# minna_schematic_io.net
KiCad netlist of a schematic drawn in Altium Designer
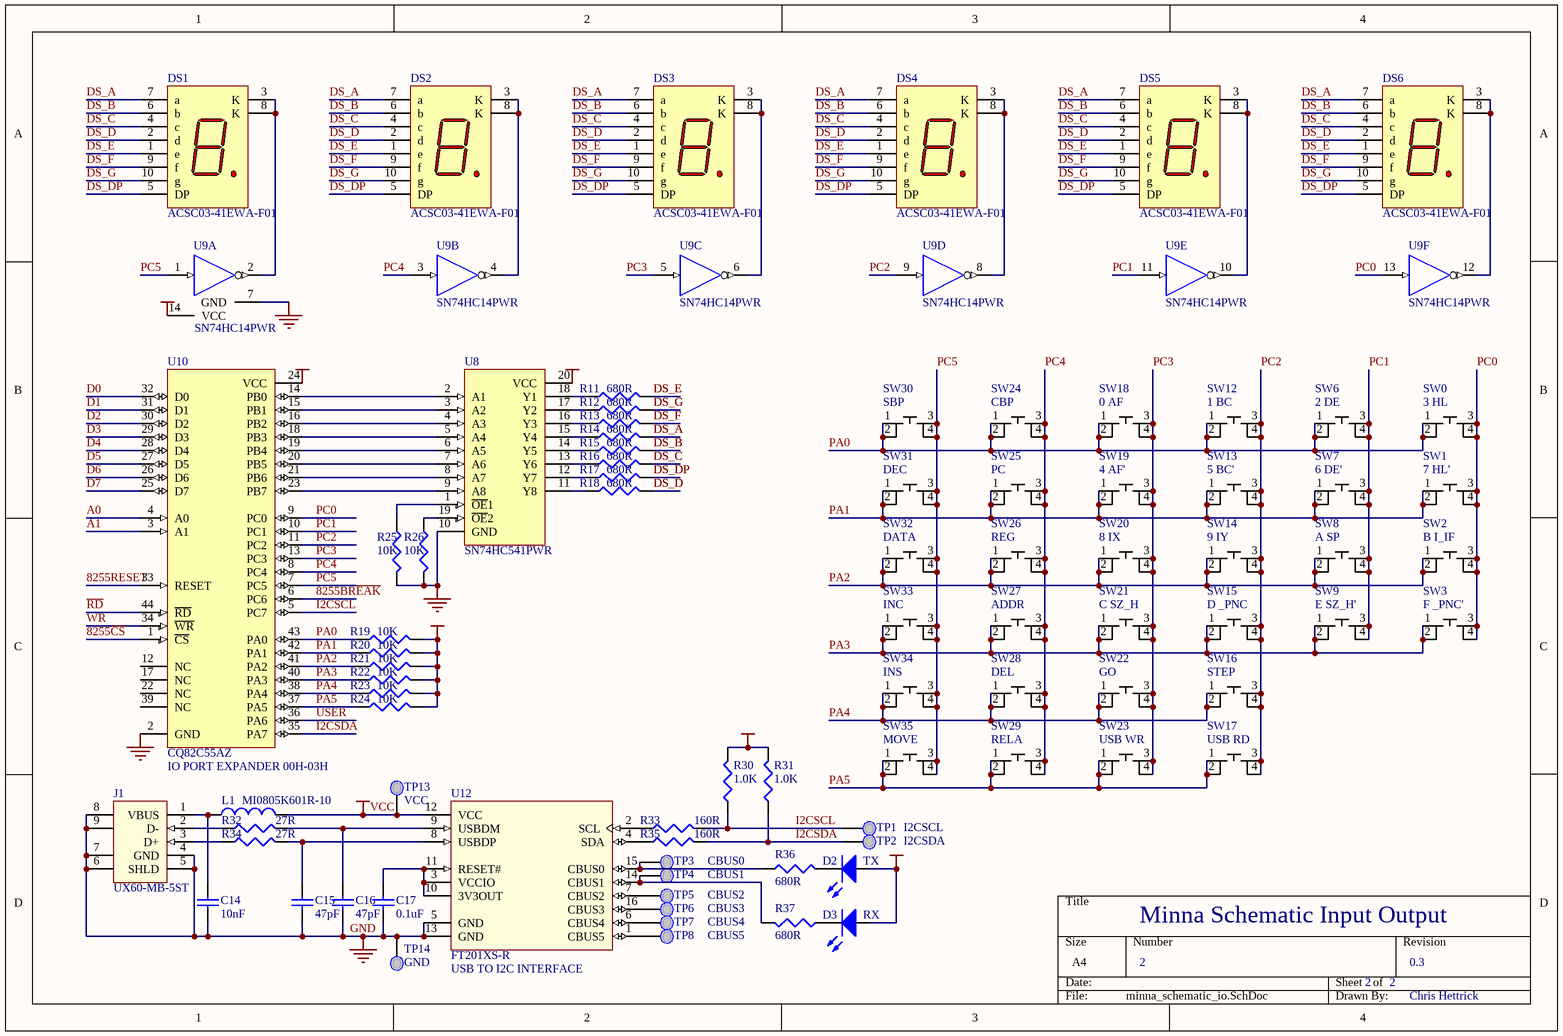
[diagram p0: minna_schematic_io.SchDoc]

(export (version "E")
  (design (tool "Eeschema 10.0.6"))
  (components
    (comp (ref "C14")
      (value "10nF")
      (footprint "smari_lib_pcb:0603")
      (description "CAP CER 10000PF 50V 10% X7R 0603")
      (libsource (lib "smari_lib_schematic") (part "C0603"))
    )
    (comp (ref "C15")
      (value "47pF")
      (footprint "smari_lib_pcb:0603")
      (description "CAP CER 47PF 50V 5% NP0 0603")
      (libsource (lib "smari_lib_schematic") (part "C0603"))
    )
    (comp (ref "C16")
      (value "47pF")
      (footprint "smari_lib_pcb:0603")
      (description "CAP CER 47PF 50V 5% NP0 0603")
      (libsource (lib "smari_lib_schematic") (part "C0603"))
    )
    (comp (ref "C17")
      (value "0.1uF")
      (footprint "smari_lib_pcb:0603")
      (description "CAP .10UF 16V CERAMIC X7R 0603")
      (libsource (lib "smari_lib_schematic") (part "C0603"))
    )
    (comp (ref "D2")
      (value "TX")
      (footprint "smari_lib_pcb:APG1608")
      (description "LED SUPER RED CLEAR 0603 SMD")
      (libsource (lib "smari_lib_schematic") (part "LTST-C190KRKT"))
    )
    (comp (ref "D3")
      (value "RX")
      (footprint "smari_lib_pcb:APG1608")
      (description "LED SUPER RED CLEAR 0603 SMD")
      (libsource (lib "smari_lib_schematic") (part "LTST-C190KRKT"))
    )
    (comp (ref "DS1")
      (value "ACSC03-41EWA-F01")
      (footprint "Minna Project:ACSC03-41EWA-F01")
      (description "DISPLAY 0.3\" 627NM SGL RED SMD")
      (libsource (lib "smari_lib_schematic") (part "ACSC03-41EWA-F01"))
    )
    (comp (ref "DS2")
      (value "ACSC03-41EWA-F01")
      (footprint "Minna Project:ACSC03-41EWA-F01")
      (description "DISPLAY 0.3\" 627NM SGL RED SMD")
      (libsource (lib "smari_lib_schematic") (part "ACSC03-41EWA-F01"))
    )
    (comp (ref "DS3")
      (value "ACSC03-41EWA-F01")
      (footprint "Minna Project:ACSC03-41EWA-F01")
      (description "DISPLAY 0.3\" 627NM SGL RED SMD")
      (libsource (lib "smari_lib_schematic") (part "ACSC03-41EWA-F01"))
    )
    (comp (ref "DS4")
      (value "ACSC03-41EWA-F01")
      (footprint "Minna Project:ACSC03-41EWA-F01")
      (description "DISPLAY 0.3\" 627NM SGL RED SMD")
      (libsource (lib "smari_lib_schematic") (part "ACSC03-41EWA-F01"))
    )
    (comp (ref "DS5")
      (value "ACSC03-41EWA-F01")
      (footprint "Minna Project:ACSC03-41EWA-F01")
      (description "DISPLAY 0.3\" 627NM SGL RED SMD")
      (libsource (lib "smari_lib_schematic") (part "ACSC03-41EWA-F01"))
    )
    (comp (ref "DS6")
      (value "ACSC03-41EWA-F01")
      (footprint "Minna Project:ACSC03-41EWA-F01")
      (description "DISPLAY 0.3\" 627NM SGL RED SMD")
      (libsource (lib "smari_lib_schematic") (part "ACSC03-41EWA-F01"))
    )
    (comp (ref "J1")
      (value "UX60-MB-5ST")
      (footprint "smari_lib_pcb:UX60-MB-5ST")
      (description "CONN RECEPT MINI USB2.0 5POS")
      (libsource (lib "smari_lib_schematic") (part "UX60-MB-5ST"))
    )
    (comp (ref "L1")
      (value "MI0805K601R-10")
      (footprint "smari_lib_pcb:0805")
      (description "FERRITE CHIP POWER 600 OHM SMD")
      (libsource (lib "smari_lib_schematic") (part "MI0805K601R-10"))
    )
    (comp (ref "R11")
      (value "680R")
      (footprint "Minna Project:0603")
      (description "RES 680 OHM 1/10W 1% 0603 SMD")
      (libsource (lib "smari_lib_schematic") (part "MCR03EZPFX"))
    )
    (comp (ref "R12")
      (value "680R")
      (footprint "Minna Project:0603")
      (description "RES 680 OHM 1/10W 1% 0603 SMD")
      (libsource (lib "smari_lib_schematic") (part "MCR03EZPFX"))
    )
    (comp (ref "R13")
      (value "680R")
      (footprint "Minna Project:0603")
      (description "RES 680 OHM 1/10W 1% 0603 SMD")
      (libsource (lib "smari_lib_schematic") (part "MCR03EZPFX"))
    )
    (comp (ref "R14")
      (value "680R")
      (footprint "Minna Project:0603")
      (description "RES 680 OHM 1/10W 1% 0603 SMD")
      (libsource (lib "smari_lib_schematic") (part "MCR03EZPFX"))
    )
    (comp (ref "R15")
      (value "680R")
      (footprint "Minna Project:0603")
      (description "RES 680 OHM 1/10W 1% 0603 SMD")
      (libsource (lib "smari_lib_schematic") (part "MCR03EZPFX"))
    )
    (comp (ref "R16")
      (value "680R")
      (footprint "Minna Project:0603")
      (description "RES 680 OHM 1/10W 1% 0603 SMD")
      (libsource (lib "smari_lib_schematic") (part "MCR03EZPFX"))
    )
    (comp (ref "R17")
      (value "680R")
      (footprint "Minna Project:0603")
      (description "RES 680 OHM 1/10W 1% 0603 SMD")
      (libsource (lib "smari_lib_schematic") (part "MCR03EZPFX"))
    )
    (comp (ref "R18")
      (value "680R")
      (footprint "Minna Project:0603")
      (description "RES 680 OHM 1/10W 1% 0603 SMD")
      (libsource (lib "smari_lib_schematic") (part "MCR03EZPFX"))
    )
    (comp (ref "R19")
      (value "10K")
      (footprint "Minna Project:0603")
      (description "RES 10.0K OHM 1/10W 1% 0603 SMD")
      (libsource (lib "smari_lib_schematic") (part "MCR03EZPFX"))
    )
    (comp (ref "R20")
      (value "10K")
      (footprint "Minna Project:0603")
      (description "RES 10.0K OHM 1/10W 1% 0603 SMD")
      (libsource (lib "smari_lib_schematic") (part "MCR03EZPFX"))
    )
    (comp (ref "R21")
      (value "10K")
      (footprint "Minna Project:0603")
      (description "RES 10.0K OHM 1/10W 1% 0603 SMD")
      (libsource (lib "smari_lib_schematic") (part "MCR03EZPFX"))
    )
    (comp (ref "R22")
      (value "10K")
      (footprint "Minna Project:0603")
      (description "RES 10.0K OHM 1/10W 1% 0603 SMD")
      (libsource (lib "smari_lib_schematic") (part "MCR03EZPFX"))
    )
    (comp (ref "R23")
      (value "10K")
      (footprint "Minna Project:0603")
      (description "RES 10.0K OHM 1/10W 1% 0603 SMD")
      (libsource (lib "smari_lib_schematic") (part "MCR03EZPFX"))
    )
    (comp (ref "R24")
      (value "10K")
      (footprint "Minna Project:0603")
      (description "RES 10.0K OHM 1/10W 1% 0603 SMD")
      (libsource (lib "smari_lib_schematic") (part "MCR03EZPFX"))
    )
    (comp (ref "R25")
      (value "10K")
      (footprint "Minna Project:0603")
      (description "RES 10.0K OHM 1/10W 1% 0603 SMD")
      (libsource (lib "smari_lib_schematic") (part "MCR03EZPFX"))
    )
    (comp (ref "R26")
      (value "10K")
      (footprint "Minna Project:0603")
      (description "RES 10.0K OHM 1/10W 1% 0603 SMD")
      (libsource (lib "smari_lib_schematic") (part "MCR03EZPFX"))
    )
    (comp (ref "R30")
      (value "1.0K")
      (footprint "smari_lib_pcb:0603")
      (description "RES 1.00K OHM 1/10W 1% 0603 SMD")
      (libsource (lib "smari_lib_schematic") (part "ERJ-3EKF1002V"))
    )
    (comp (ref "R31")
      (value "1.0K")
      (footprint "smari_lib_pcb:0603")
      (description "RES 1.00K OHM 1/10W 1% 0603 SMD")
      (libsource (lib "smari_lib_schematic") (part "ERJ-3EKF1002V"))
    )
    (comp (ref "R32")
      (value "27R")
      (footprint "smari_lib_pcb:0603")
      (description "RES 27.0 OHM 1/10W 1% 0603 SMD")
      (libsource (lib "smari_lib_schematic") (part "ERJ-3EKF1002V"))
    )
    (comp (ref "R33")
      (value "160R")
      (footprint "smari_lib_pcb:0603")
      (description "RES 160 OHM 1/10W 1% 0603 SMD")
      (libsource (lib "smari_lib_schematic") (part "ERJ-3EKF1002V"))
    )
    (comp (ref "R34")
      (value "27R")
      (footprint "smari_lib_pcb:0603")
      (description "RES 27.0 OHM 1/10W 1% 0603 SMD")
      (libsource (lib "smari_lib_schematic") (part "ERJ-3EKF1002V"))
    )
    (comp (ref "R35")
      (value "160R")
      (footprint "smari_lib_pcb:0603")
      (description "RES 160 OHM 1/10W 1% 0603 SMD")
      (libsource (lib "smari_lib_schematic") (part "ERJ-3EKF1002V"))
    )
    (comp (ref "R36")
      (value "680R")
      (footprint "smari_lib_pcb:0603")
      (description "RES 680 OHM 1/10W 1% 0603 SMD")
      (libsource (lib "smari_lib_schematic") (part "MCR03EZPFX"))
    )
    (comp (ref "R37")
      (value "680R")
      (footprint "smari_lib_pcb:0603")
      (description "RES 680 OHM 1/10W 1% 0603 SMD")
      (libsource (lib "smari_lib_schematic") (part "MCR03EZPFX"))
    )
    (comp (ref "SW0")
      (value "3 HL")
      (footprint "Minna Project:PTS645SM43SMTR LFS")
      (description "SWITCH TACT 6MM 160GF H=4.3MM")
      (libsource (lib "smari_lib_schematic") (part "PTS645SM43SMTR LFS"))
    )
    (comp (ref "SW1")
      (value "7 HL'")
      (footprint "Minna Project:PTS645SM43SMTR LFS")
      (description "SWITCH TACT 6MM 160GF H=4.3MM")
      (libsource (lib "smari_lib_schematic") (part "PTS645SM43SMTR LFS"))
    )
    (comp (ref "SW2")
      (value "B I_IF")
      (footprint "Minna Project:PTS645SM43SMTR LFS")
      (description "SWITCH TACT 6MM 160GF H=4.3MM")
      (libsource (lib "smari_lib_schematic") (part "PTS645SM43SMTR LFS"))
    )
    (comp (ref "SW3")
      (value "F _PNC'")
      (footprint "Minna Project:PTS645SM43SMTR LFS")
      (description "SWITCH TACT 6MM 160GF H=4.3MM")
      (libsource (lib "smari_lib_schematic") (part "PTS645SM43SMTR LFS"))
    )
    (comp (ref "SW6")
      (value "2 DE")
      (footprint "Minna Project:PTS645SM43SMTR LFS")
      (description "SWITCH TACT 6MM 160GF H=4.3MM")
      (libsource (lib "smari_lib_schematic") (part "PTS645SM43SMTR LFS"))
    )
    (comp (ref "SW7")
      (value "6 DE'")
      (footprint "Minna Project:PTS645SM43SMTR LFS")
      (description "SWITCH TACT 6MM 160GF H=4.3MM")
      (libsource (lib "smari_lib_schematic") (part "PTS645SM43SMTR LFS"))
    )
    (comp (ref "SW8")
      (value "A SP")
      (footprint "Minna Project:PTS645SM43SMTR LFS")
      (description "SWITCH TACT 6MM 160GF H=4.3MM")
      (libsource (lib "smari_lib_schematic") (part "PTS645SM43SMTR LFS"))
    )
    (comp (ref "SW9")
      (value "E SZ_H'")
      (footprint "Minna Project:PTS645SM43SMTR LFS")
      (description "SWITCH TACT 6MM 160GF H=4.3MM")
      (libsource (lib "smari_lib_schematic") (part "PTS645SM43SMTR LFS"))
    )
    (comp (ref "SW12")
      (value "1 BC")
      (footprint "Minna Project:PTS645SM43SMTR LFS")
      (description "SWITCH TACT 6MM 160GF H=4.3MM")
      (libsource (lib "smari_lib_schematic") (part "PTS645SM43SMTR LFS"))
    )
    (comp (ref "SW13")
      (value "5 BC'")
      (footprint "Minna Project:PTS645SM43SMTR LFS")
      (description "SWITCH TACT 6MM 160GF H=4.3MM")
      (libsource (lib "smari_lib_schematic") (part "PTS645SM43SMTR LFS"))
    )
    (comp (ref "SW14")
      (value "9 IY")
      (footprint "Minna Project:PTS645SM43SMTR LFS")
      (description "SWITCH TACT 6MM 160GF H=4.3MM")
      (libsource (lib "smari_lib_schematic") (part "PTS645SM43SMTR LFS"))
    )
    (comp (ref "SW15")
      (value "D _PNC")
      (footprint "Minna Project:PTS645SM43SMTR LFS")
      (description "SWITCH TACT 6MM 160GF H=4.3MM")
      (libsource (lib "smari_lib_schematic") (part "PTS645SM43SMTR LFS"))
    )
    (comp (ref "SW16")
      (value "STEP")
      (footprint "Minna Project:PTS645SM43SMTR LFS")
      (description "SWITCH TACT 6MM 160GF H=4.3MM")
      (libsource (lib "smari_lib_schematic") (part "PTS645SM43SMTR LFS"))
    )
    (comp (ref "SW17")
      (value "USB RD")
      (footprint "Minna Project:PTS645SM43SMTR LFS")
      (description "SWITCH TACT 6MM 160GF H=4.3MM")
      (libsource (lib "smari_lib_schematic") (part "PTS645SM43SMTR LFS"))
    )
    (comp (ref "SW18")
      (value "0 AF")
      (footprint "Minna Project:PTS645SM43SMTR LFS")
      (description "SWITCH TACT 6MM 160GF H=4.3MM")
      (libsource (lib "smari_lib_schematic") (part "PTS645SM43SMTR LFS"))
    )
    (comp (ref "SW19")
      (value "4 AF'")
      (footprint "Minna Project:PTS645SM43SMTR LFS")
      (description "SWITCH TACT 6MM 160GF H=4.3MM")
      (libsource (lib "smari_lib_schematic") (part "PTS645SM43SMTR LFS"))
    )
    (comp (ref "SW20")
      (value "8 IX")
      (footprint "Minna Project:PTS645SM43SMTR LFS")
      (description "SWITCH TACT 6MM 160GF H=4.3MM")
      (libsource (lib "smari_lib_schematic") (part "PTS645SM43SMTR LFS"))
    )
    (comp (ref "SW21")
      (value "C SZ_H")
      (footprint "Minna Project:PTS645SM43SMTR LFS")
      (description "SWITCH TACT 6MM 160GF H=4.3MM")
      (libsource (lib "smari_lib_schematic") (part "PTS645SM43SMTR LFS"))
    )
    (comp (ref "SW22")
      (value "GO")
      (footprint "Minna Project:PTS645SM43SMTR LFS")
      (description "SWITCH TACT 6MM 160GF H=4.3MM")
      (libsource (lib "smari_lib_schematic") (part "PTS645SM43SMTR LFS"))
    )
    (comp (ref "SW23")
      (value "USB WR")
      (footprint "Minna Project:PTS645SM43SMTR LFS")
      (description "SWITCH TACT 6MM 160GF H=4.3MM")
      (libsource (lib "smari_lib_schematic") (part "PTS645SM43SMTR LFS"))
    )
    (comp (ref "SW24")
      (value "CBP")
      (footprint "Minna Project:PTS645SM43SMTR LFS")
      (description "SWITCH TACT 6MM 160GF H=4.3MM")
      (libsource (lib "smari_lib_schematic") (part "PTS645SM43SMTR LFS"))
    )
    (comp (ref "SW25")
      (value "PC")
      (footprint "Minna Project:PTS645SM43SMTR LFS")
      (description "SWITCH TACT 6MM 160GF H=4.3MM")
      (libsource (lib "smari_lib_schematic") (part "PTS645SM43SMTR LFS"))
    )
    (comp (ref "SW26")
      (value "REG")
      (footprint "Minna Project:PTS645SM43SMTR LFS")
      (description "SWITCH TACT 6MM 160GF H=4.3MM")
      (libsource (lib "smari_lib_schematic") (part "PTS645SM43SMTR LFS"))
    )
    (comp (ref "SW27")
      (value "ADDR")
      (footprint "Minna Project:PTS645SM43SMTR LFS")
      (description "SWITCH TACT 6MM 160GF H=4.3MM")
      (libsource (lib "smari_lib_schematic") (part "PTS645SM43SMTR LFS"))
    )
    (comp (ref "SW28")
      (value "DEL")
      (footprint "Minna Project:PTS645SM43SMTR LFS")
      (description "SWITCH TACT 6MM 160GF H=4.3MM")
      (libsource (lib "smari_lib_schematic") (part "PTS645SM43SMTR LFS"))
    )
    (comp (ref "SW29")
      (value "RELA")
      (footprint "Minna Project:PTS645SM43SMTR LFS")
      (description "SWITCH TACT 6MM 160GF H=4.3MM")
      (libsource (lib "smari_lib_schematic") (part "PTS645SM43SMTR LFS"))
    )
    (comp (ref "SW30")
      (value "SBP")
      (footprint "Minna Project:PTS645SM43SMTR LFS")
      (description "SWITCH TACT 6MM 160GF H=4.3MM")
      (libsource (lib "smari_lib_schematic") (part "PTS645SM43SMTR LFS"))
    )
    (comp (ref "SW31")
      (value "DEC")
      (footprint "Minna Project:PTS645SM43SMTR LFS")
      (description "SWITCH TACT 6MM 160GF H=4.3MM")
      (libsource (lib "smari_lib_schematic") (part "PTS645SM43SMTR LFS"))
    )
    (comp (ref "SW32")
      (value "DATA")
      (footprint "Minna Project:PTS645SM43SMTR LFS")
      (description "SWITCH TACT 6MM 160GF H=4.3MM")
      (libsource (lib "smari_lib_schematic") (part "PTS645SM43SMTR LFS"))
    )
    (comp (ref "SW33")
      (value "INC")
      (footprint "Minna Project:PTS645SM43SMTR LFS")
      (description "SWITCH TACT 6MM 160GF H=4.3MM")
      (libsource (lib "smari_lib_schematic") (part "PTS645SM43SMTR LFS"))
    )
    (comp (ref "SW34")
      (value "INS")
      (footprint "Minna Project:PTS645SM43SMTR LFS")
      (description "SWITCH TACT 6MM 160GF H=4.3MM")
      (libsource (lib "smari_lib_schematic") (part "PTS645SM43SMTR LFS"))
    )
    (comp (ref "SW35")
      (value "MOVE")
      (footprint "Minna Project:PTS645SM43SMTR LFS")
      (description "SWITCH TACT 6MM 160GF H=4.3MM")
      (libsource (lib "smari_lib_schematic") (part "PTS645SM43SMTR LFS"))
    )
    (comp (ref "TP1")
      (value "I2CSCL")
      (footprint "smari_lib_pcb:TP_ICT")
      (description "TEST POINT")
      (libsource (lib "smari_lib_schematic") (part "TP_ICT"))
    )
    (comp (ref "TP2")
      (value "I2CSDA")
      (footprint "smari_lib_pcb:TP_ICT")
      (description "TEST POINT")
      (libsource (lib "smari_lib_schematic") (part "TP_ICT"))
    )
    (comp (ref "TP3")
      (value "CBUS0")
      (footprint "smari_lib_pcb:TP_ICT")
      (description "TEST POINT")
      (libsource (lib "smari_lib_schematic") (part "TP_ICT"))
    )
    (comp (ref "TP4")
      (value "CBUS1")
      (footprint "smari_lib_pcb:TP_ICT")
      (description "TEST POINT")
      (libsource (lib "smari_lib_schematic") (part "TP_ICT"))
    )
    (comp (ref "TP5")
      (value "CBUS2")
      (footprint "smari_lib_pcb:TP_ICT")
      (description "TEST POINT")
      (libsource (lib "smari_lib_schematic") (part "TP_ICT"))
    )
    (comp (ref "TP6")
      (value "CBUS3")
      (footprint "smari_lib_pcb:TP_ICT")
      (description "TEST POINT")
      (libsource (lib "smari_lib_schematic") (part "TP_ICT"))
    )
    (comp (ref "TP7")
      (value "CBUS4")
      (footprint "smari_lib_pcb:TP_ICT")
      (description "TEST POINT")
      (libsource (lib "smari_lib_schematic") (part "TP_ICT"))
    )
    (comp (ref "TP8")
      (value "CBUS5")
      (footprint "smari_lib_pcb:TP_ICT")
      (description "TEST POINT")
      (libsource (lib "smari_lib_schematic") (part "TP_ICT"))
    )
    (comp (ref "TP13")
      (value "VCC")
      (footprint "smari_lib_pcb:TP_ICT")
      (description "TEST POINT")
      (libsource (lib "smari_lib_schematic") (part "TP_ICT"))
    )
    (comp (ref "TP14")
      (value "GND")
      (footprint "smari_lib_pcb:TP_ICT")
      (description "TEST POINT")
      (libsource (lib "smari_lib_schematic") (part "TP_ICT"))
    )
    (comp (ref "U8")
      (value "SN74HC541PWR")
      (footprint "Minna Project:PW020")
      (description "IC BUFF/DVR TRI-ST 8BIT 20TSSOP")
      (libsource (lib "smari_lib_schematic") (part "SN74HC541PWR"))
    )
    (comp (ref "U9")
      (value "SN74HC14PWR")
      (footprint "Minna Project:PW014")
      (description "IC HEX SCHMITT-TRIG INV 14-TSSOP")
      (libsource (lib "") (part "SN74HC14PWR_1"))
    )
    (comp (ref "U10")
      (value "CQ82C55AZ")
      (footprint "Minna Project:MQFP-44")
      (description "IC I/O EXPANDER 24B 44MQFP")
      (fields (field (name "NOTES") "IO PORT EXPANDER 00H-03H"))
      (libsource (lib "smari_lib_schematic") (part "CMQ82C55AZ"))
    )
    (comp (ref "U12")
      (value "FT201XS-R")
      (footprint "smari_lib_pcb:SSOP-16")
      (description "IC USB FS I2C SSOP-16")
      (fields (field (name "NOTES") "USB TO I2C INTERFACE"))
      (libsource (lib "smari_lib_schematic") (part "FT201XS-R"))
    )
  )
  (nets
    (net (code "1") (name "/8255RESET") (class "Default")
      (node (ref "U10") (pin "33") (pinfunction "RESET_33") (pintype "input"))
    )
    (net (code "2") (name "/8255~{BREAK}") (class "Default")
      (node (ref "U10") (pin "6") (pinfunction "PC6_6") (pintype "bidirectional"))
    )
    (net (code "3") (name "/8255~{CS}") (class "Default")
      (node (ref "U10") (pin "1") (pinfunction "~{CS}_1") (pintype "input"))
    )
    (net (code "4") (name "/A0") (class "Default")
      (node (ref "U10") (pin "4") (pinfunction "A0_4") (pintype "input"))
    )
    (net (code "5") (name "/A1") (class "Default")
      (node (ref "U10") (pin "3") (pinfunction "A1_3") (pintype "input"))
    )
    (net (code "6") (name "/D0") (class "Default")
      (node (ref "U10") (pin "32") (pinfunction "D0_32") (pintype "bidirectional"))
    )
    (net (code "7") (name "/D1") (class "Default")
      (node (ref "U10") (pin "31") (pinfunction "D1_31") (pintype "bidirectional"))
    )
    (net (code "8") (name "/D2") (class "Default")
      (node (ref "U10") (pin "30") (pinfunction "D2_30") (pintype "bidirectional"))
    )
    (net (code "9") (name "/D3") (class "Default")
      (node (ref "U10") (pin "29") (pinfunction "D3_29") (pintype "bidirectional"))
    )
    (net (code "10") (name "/D4") (class "Default")
      (node (ref "U10") (pin "28") (pinfunction "D4_28") (pintype "bidirectional"))
    )
    (net (code "11") (name "/D5") (class "Default")
      (node (ref "U10") (pin "27") (pinfunction "D5_27") (pintype "bidirectional"))
    )
    (net (code "12") (name "/D6") (class "Default")
      (node (ref "U10") (pin "26") (pinfunction "D6_26") (pintype "bidirectional"))
    )
    (net (code "13") (name "/D7") (class "Default")
      (node (ref "U10") (pin "25") (pinfunction "D7_25") (pintype "bidirectional"))
    )
    (net (code "14") (name "/DS_A") (class "Default")
      (node (ref "DS1") (pin "7") (pinfunction "a_7") (pintype "passive"))
      (node (ref "DS2") (pin "7") (pinfunction "a_7") (pintype "passive"))
      (node (ref "DS3") (pin "7") (pinfunction "a_7") (pintype "passive"))
      (node (ref "DS4") (pin "7") (pinfunction "a_7") (pintype "passive"))
      (node (ref "DS5") (pin "7") (pinfunction "a_7") (pintype "passive"))
      (node (ref "DS6") (pin "7") (pinfunction "a_7") (pintype "passive"))
      (node (ref "R14") (pin "2") (pinfunction "2_2") (pintype "passive"))
    )
    (net (code "15") (name "/DS_B") (class "Default")
      (node (ref "DS1") (pin "6") (pinfunction "b_6") (pintype "passive"))
      (node (ref "DS2") (pin "6") (pinfunction "b_6") (pintype "passive"))
      (node (ref "DS3") (pin "6") (pinfunction "b_6") (pintype "passive"))
      (node (ref "DS4") (pin "6") (pinfunction "b_6") (pintype "passive"))
      (node (ref "DS5") (pin "6") (pinfunction "b_6") (pintype "passive"))
      (node (ref "DS6") (pin "6") (pinfunction "b_6") (pintype "passive"))
      (node (ref "R15") (pin "2") (pinfunction "2_2") (pintype "passive"))
    )
    (net (code "16") (name "/DS_C") (class "Default")
      (node (ref "DS1") (pin "4") (pinfunction "c_4") (pintype "passive"))
      (node (ref "DS2") (pin "4") (pinfunction "c_4") (pintype "passive"))
      (node (ref "DS3") (pin "4") (pinfunction "c_4") (pintype "passive"))
      (node (ref "DS4") (pin "4") (pinfunction "c_4") (pintype "passive"))
      (node (ref "DS5") (pin "4") (pinfunction "c_4") (pintype "passive"))
      (node (ref "DS6") (pin "4") (pinfunction "c_4") (pintype "passive"))
      (node (ref "R16") (pin "2") (pinfunction "2_2") (pintype "passive"))
    )
    (net (code "17") (name "/DS_D") (class "Default")
      (node (ref "DS1") (pin "2") (pinfunction "d_2") (pintype "passive"))
      (node (ref "DS2") (pin "2") (pinfunction "d_2") (pintype "passive"))
      (node (ref "DS3") (pin "2") (pinfunction "d_2") (pintype "passive"))
      (node (ref "DS4") (pin "2") (pinfunction "d_2") (pintype "passive"))
      (node (ref "DS5") (pin "2") (pinfunction "d_2") (pintype "passive"))
      (node (ref "DS6") (pin "2") (pinfunction "d_2") (pintype "passive"))
      (node (ref "R18") (pin "2") (pinfunction "2_2") (pintype "passive"))
    )
    (net (code "18") (name "/DS_DP") (class "Default")
      (node (ref "DS1") (pin "5") (pinfunction "DP_5") (pintype "passive"))
      (node (ref "DS2") (pin "5") (pinfunction "DP_5") (pintype "passive"))
      (node (ref "DS3") (pin "5") (pinfunction "DP_5") (pintype "passive"))
      (node (ref "DS4") (pin "5") (pinfunction "DP_5") (pintype "passive"))
      (node (ref "DS5") (pin "5") (pinfunction "DP_5") (pintype "passive"))
      (node (ref "DS6") (pin "5") (pinfunction "DP_5") (pintype "passive"))
      (node (ref "R17") (pin "2") (pinfunction "2_2") (pintype "passive"))
    )
    (net (code "19") (name "/DS_E") (class "Default")
      (node (ref "DS1") (pin "1") (pinfunction "e_1") (pintype "passive"))
      (node (ref "DS2") (pin "1") (pinfunction "e_1") (pintype "passive"))
      (node (ref "DS3") (pin "1") (pinfunction "e_1") (pintype "passive"))
      (node (ref "DS4") (pin "1") (pinfunction "e_1") (pintype "passive"))
      (node (ref "DS5") (pin "1") (pinfunction "e_1") (pintype "passive"))
      (node (ref "DS6") (pin "1") (pinfunction "e_1") (pintype "passive"))
      (node (ref "R11") (pin "2") (pinfunction "2_2") (pintype "passive"))
    )
    (net (code "20") (name "/DS_F") (class "Default")
      (node (ref "DS1") (pin "9") (pinfunction "f_9") (pintype "passive"))
      (node (ref "DS2") (pin "9") (pinfunction "f_9") (pintype "passive"))
      (node (ref "DS3") (pin "9") (pinfunction "f_9") (pintype "passive"))
      (node (ref "DS4") (pin "9") (pinfunction "f_9") (pintype "passive"))
      (node (ref "DS5") (pin "9") (pinfunction "f_9") (pintype "passive"))
      (node (ref "DS6") (pin "9") (pinfunction "f_9") (pintype "passive"))
      (node (ref "R13") (pin "2") (pinfunction "2_2") (pintype "passive"))
    )
    (net (code "21") (name "/DS_G") (class "Default")
      (node (ref "DS1") (pin "10") (pinfunction "g_10") (pintype "passive"))
      (node (ref "DS2") (pin "10") (pinfunction "g_10") (pintype "passive"))
      (node (ref "DS3") (pin "10") (pinfunction "g_10") (pintype "passive"))
      (node (ref "DS4") (pin "10") (pinfunction "g_10") (pintype "passive"))
      (node (ref "DS5") (pin "10") (pinfunction "g_10") (pintype "passive"))
      (node (ref "DS6") (pin "10") (pinfunction "g_10") (pintype "passive"))
      (node (ref "R12") (pin "2") (pinfunction "2_2") (pintype "passive"))
    )
    (net (code "22") (name "/I2CSCL") (class "Default")
      (node (ref "R30") (pin "1") (pinfunction "1_1") (pintype "passive"))
      (node (ref "R33") (pin "2") (pinfunction "2_2") (pintype "passive"))
      (node (ref "TP1") (pin "TP") (pinfunction "TP_TP") (pintype "passive"))
      (node (ref "U10") (pin "5") (pinfunction "PC7_5") (pintype "bidirectional"))
    )
    (net (code "23") (name "/I2CSDA") (class "Default")
      (node (ref "R31") (pin "1") (pinfunction "1_1") (pintype "passive"))
      (node (ref "R35") (pin "2") (pinfunction "2_2") (pintype "passive"))
      (node (ref "TP2") (pin "TP") (pinfunction "TP_TP") (pintype "passive"))
      (node (ref "U10") (pin "35") (pinfunction "PA7_35") (pintype "bidirectional"))
    )
    (net (code "24") (name "/PA0") (class "Default")
      (node (ref "R19") (pin "1") (pinfunction "1_1") (pintype "passive"))
      (node (ref "SW0") (pin "1") (pinfunction "1_1") (pintype "passive"))
      (node (ref "SW0") (pin "2") (pinfunction "2_2") (pintype "passive"))
      (node (ref "SW12") (pin "1") (pinfunction "1_1") (pintype "passive"))
      (node (ref "SW12") (pin "2") (pinfunction "2_2") (pintype "passive"))
      (node (ref "SW18") (pin "1") (pinfunction "1_1") (pintype "passive"))
      (node (ref "SW18") (pin "2") (pinfunction "2_2") (pintype "passive"))
      (node (ref "SW24") (pin "1") (pinfunction "1_1") (pintype "passive"))
      (node (ref "SW24") (pin "2") (pinfunction "2_2") (pintype "passive"))
      (node (ref "SW30") (pin "1") (pinfunction "1_1") (pintype "passive"))
      (node (ref "SW30") (pin "2") (pinfunction "2_2") (pintype "passive"))
      (node (ref "SW6") (pin "1") (pinfunction "1_1") (pintype "passive"))
      (node (ref "SW6") (pin "2") (pinfunction "2_2") (pintype "passive"))
      (node (ref "U10") (pin "43") (pinfunction "PA0_43") (pintype "bidirectional"))
    )
    (net (code "25") (name "/PA1") (class "Default")
      (node (ref "R20") (pin "1") (pinfunction "1_1") (pintype "passive"))
      (node (ref "SW1") (pin "1") (pinfunction "1_1") (pintype "passive"))
      (node (ref "SW1") (pin "2") (pinfunction "2_2") (pintype "passive"))
      (node (ref "SW13") (pin "1") (pinfunction "1_1") (pintype "passive"))
      (node (ref "SW13") (pin "2") (pinfunction "2_2") (pintype "passive"))
      (node (ref "SW19") (pin "1") (pinfunction "1_1") (pintype "passive"))
      (node (ref "SW19") (pin "2") (pinfunction "2_2") (pintype "passive"))
      (node (ref "SW25") (pin "1") (pinfunction "1_1") (pintype "passive"))
      (node (ref "SW25") (pin "2") (pinfunction "2_2") (pintype "passive"))
      (node (ref "SW31") (pin "1") (pinfunction "1_1") (pintype "passive"))
      (node (ref "SW31") (pin "2") (pinfunction "2_2") (pintype "passive"))
      (node (ref "SW7") (pin "1") (pinfunction "1_1") (pintype "passive"))
      (node (ref "SW7") (pin "2") (pinfunction "2_2") (pintype "passive"))
      (node (ref "U10") (pin "42") (pinfunction "PA1_42") (pintype "bidirectional"))
    )
    (net (code "26") (name "/PA2") (class "Default")
      (node (ref "R21") (pin "1") (pinfunction "1_1") (pintype "passive"))
      (node (ref "SW14") (pin "1") (pinfunction "1_1") (pintype "passive"))
      (node (ref "SW14") (pin "2") (pinfunction "2_2") (pintype "passive"))
      (node (ref "SW2") (pin "1") (pinfunction "1_1") (pintype "passive"))
      (node (ref "SW2") (pin "2") (pinfunction "2_2") (pintype "passive"))
      (node (ref "SW20") (pin "1") (pinfunction "1_1") (pintype "passive"))
      (node (ref "SW20") (pin "2") (pinfunction "2_2") (pintype "passive"))
      (node (ref "SW26") (pin "1") (pinfunction "1_1") (pintype "passive"))
      (node (ref "SW26") (pin "2") (pinfunction "2_2") (pintype "passive"))
      (node (ref "SW32") (pin "1") (pinfunction "1_1") (pintype "passive"))
      (node (ref "SW32") (pin "2") (pinfunction "2_2") (pintype "passive"))
      (node (ref "SW8") (pin "1") (pinfunction "1_1") (pintype "passive"))
      (node (ref "SW8") (pin "2") (pinfunction "2_2") (pintype "passive"))
      (node (ref "U10") (pin "41") (pinfunction "PA2_41") (pintype "bidirectional"))
    )
    (net (code "27") (name "/PA3") (class "Default")
      (node (ref "R22") (pin "1") (pinfunction "1_1") (pintype "passive"))
      (node (ref "SW15") (pin "1") (pinfunction "1_1") (pintype "passive"))
      (node (ref "SW15") (pin "2") (pinfunction "2_2") (pintype "passive"))
      (node (ref "SW21") (pin "1") (pinfunction "1_1") (pintype "passive"))
      (node (ref "SW21") (pin "2") (pinfunction "2_2") (pintype "passive"))
      (node (ref "SW27") (pin "1") (pinfunction "1_1") (pintype "passive"))
      (node (ref "SW27") (pin "2") (pinfunction "2_2") (pintype "passive"))
      (node (ref "SW3") (pin "1") (pinfunction "1_1") (pintype "passive"))
      (node (ref "SW3") (pin "2") (pinfunction "2_2") (pintype "passive"))
      (node (ref "SW33") (pin "1") (pinfunction "1_1") (pintype "passive"))
      (node (ref "SW33") (pin "2") (pinfunction "2_2") (pintype "passive"))
      (node (ref "SW9") (pin "1") (pinfunction "1_1") (pintype "passive"))
      (node (ref "SW9") (pin "2") (pinfunction "2_2") (pintype "passive"))
      (node (ref "U10") (pin "40") (pinfunction "PA3_40") (pintype "bidirectional"))
    )
    (net (code "28") (name "/PA4") (class "Default")
      (node (ref "R23") (pin "1") (pinfunction "1_1") (pintype "passive"))
      (node (ref "SW16") (pin "1") (pinfunction "1_1") (pintype "passive"))
      (node (ref "SW16") (pin "2") (pinfunction "2_2") (pintype "passive"))
      (node (ref "SW22") (pin "1") (pinfunction "1_1") (pintype "passive"))
      (node (ref "SW22") (pin "2") (pinfunction "2_2") (pintype "passive"))
      (node (ref "SW28") (pin "1") (pinfunction "1_1") (pintype "passive"))
      (node (ref "SW28") (pin "2") (pinfunction "2_2") (pintype "passive"))
      (node (ref "SW34") (pin "1") (pinfunction "1_1") (pintype "passive"))
      (node (ref "SW34") (pin "2") (pinfunction "2_2") (pintype "passive"))
      (node (ref "U10") (pin "38") (pinfunction "PA4_38") (pintype "bidirectional"))
    )
    (net (code "29") (name "/PA5") (class "Default")
      (node (ref "R24") (pin "1") (pinfunction "1_1") (pintype "passive"))
      (node (ref "SW17") (pin "1") (pinfunction "1_1") (pintype "passive"))
      (node (ref "SW17") (pin "2") (pinfunction "2_2") (pintype "passive"))
      (node (ref "SW23") (pin "1") (pinfunction "1_1") (pintype "passive"))
      (node (ref "SW23") (pin "2") (pinfunction "2_2") (pintype "passive"))
      (node (ref "SW29") (pin "1") (pinfunction "1_1") (pintype "passive"))
      (node (ref "SW29") (pin "2") (pinfunction "2_2") (pintype "passive"))
      (node (ref "SW35") (pin "1") (pinfunction "1_1") (pintype "passive"))
      (node (ref "SW35") (pin "2") (pinfunction "2_2") (pintype "passive"))
      (node (ref "U10") (pin "37") (pinfunction "PA5_37") (pintype "bidirectional"))
    )
    (net (code "30") (name "/PC0") (class "Default")
      (node (ref "SW0") (pin "3") (pinfunction "3_3") (pintype "passive"))
      (node (ref "SW0") (pin "4") (pinfunction "4_4") (pintype "passive"))
      (node (ref "SW1") (pin "3") (pinfunction "3_3") (pintype "passive"))
      (node (ref "SW1") (pin "4") (pinfunction "4_4") (pintype "passive"))
      (node (ref "SW2") (pin "3") (pinfunction "3_3") (pintype "passive"))
      (node (ref "SW2") (pin "4") (pinfunction "4_4") (pintype "passive"))
      (node (ref "SW3") (pin "3") (pinfunction "3_3") (pintype "passive"))
      (node (ref "SW3") (pin "4") (pinfunction "4_4") (pintype "passive"))
      (node (ref "U10") (pin "9") (pinfunction "PC0_9") (pintype "bidirectional"))
      (node (ref "U9") (pin "13") (pinfunction "A_13") (pintype "input"))
    )
    (net (code "31") (name "/PC1") (class "Default")
      (node (ref "SW6") (pin "3") (pinfunction "3_3") (pintype "passive"))
      (node (ref "SW6") (pin "4") (pinfunction "4_4") (pintype "passive"))
      (node (ref "SW7") (pin "3") (pinfunction "3_3") (pintype "passive"))
      (node (ref "SW7") (pin "4") (pinfunction "4_4") (pintype "passive"))
      (node (ref "SW8") (pin "3") (pinfunction "3_3") (pintype "passive"))
      (node (ref "SW8") (pin "4") (pinfunction "4_4") (pintype "passive"))
      (node (ref "SW9") (pin "3") (pinfunction "3_3") (pintype "passive"))
      (node (ref "SW9") (pin "4") (pinfunction "4_4") (pintype "passive"))
      (node (ref "U10") (pin "10") (pinfunction "PC1_10") (pintype "bidirectional"))
      (node (ref "U9") (pin "11") (pinfunction "A_11") (pintype "input"))
    )
    (net (code "32") (name "/PC2") (class "Default")
      (node (ref "SW12") (pin "3") (pinfunction "3_3") (pintype "passive"))
      (node (ref "SW12") (pin "4") (pinfunction "4_4") (pintype "passive"))
      (node (ref "SW13") (pin "3") (pinfunction "3_3") (pintype "passive"))
      (node (ref "SW13") (pin "4") (pinfunction "4_4") (pintype "passive"))
      (node (ref "SW14") (pin "3") (pinfunction "3_3") (pintype "passive"))
      (node (ref "SW14") (pin "4") (pinfunction "4_4") (pintype "passive"))
      (node (ref "SW15") (pin "3") (pinfunction "3_3") (pintype "passive"))
      (node (ref "SW15") (pin "4") (pinfunction "4_4") (pintype "passive"))
      (node (ref "SW16") (pin "3") (pinfunction "3_3") (pintype "passive"))
      (node (ref "SW16") (pin "4") (pinfunction "4_4") (pintype "passive"))
      (node (ref "SW17") (pin "3") (pinfunction "3_3") (pintype "passive"))
      (node (ref "SW17") (pin "4") (pinfunction "4_4") (pintype "passive"))
      (node (ref "U10") (pin "11") (pinfunction "PC2_11") (pintype "bidirectional"))
      (node (ref "U9") (pin "9") (pinfunction "A_9") (pintype "input"))
    )
    (net (code "33") (name "/PC3") (class "Default")
      (node (ref "SW18") (pin "3") (pinfunction "3_3") (pintype "passive"))
      (node (ref "SW18") (pin "4") (pinfunction "4_4") (pintype "passive"))
      (node (ref "SW19") (pin "3") (pinfunction "3_3") (pintype "passive"))
      (node (ref "SW19") (pin "4") (pinfunction "4_4") (pintype "passive"))
      (node (ref "SW20") (pin "3") (pinfunction "3_3") (pintype "passive"))
      (node (ref "SW20") (pin "4") (pinfunction "4_4") (pintype "passive"))
      (node (ref "SW21") (pin "3") (pinfunction "3_3") (pintype "passive"))
      (node (ref "SW21") (pin "4") (pinfunction "4_4") (pintype "passive"))
      (node (ref "SW22") (pin "3") (pinfunction "3_3") (pintype "passive"))
      (node (ref "SW22") (pin "4") (pinfunction "4_4") (pintype "passive"))
      (node (ref "SW23") (pin "3") (pinfunction "3_3") (pintype "passive"))
      (node (ref "SW23") (pin "4") (pinfunction "4_4") (pintype "passive"))
      (node (ref "U10") (pin "13") (pinfunction "PC3_13") (pintype "bidirectional"))
      (node (ref "U9") (pin "5") (pinfunction "A_5") (pintype "input"))
    )
    (net (code "34") (name "/PC4") (class "Default")
      (node (ref "SW24") (pin "3") (pinfunction "3_3") (pintype "passive"))
      (node (ref "SW24") (pin "4") (pinfunction "4_4") (pintype "passive"))
      (node (ref "SW25") (pin "3") (pinfunction "3_3") (pintype "passive"))
      (node (ref "SW25") (pin "4") (pinfunction "4_4") (pintype "passive"))
      (node (ref "SW26") (pin "3") (pinfunction "3_3") (pintype "passive"))
      (node (ref "SW26") (pin "4") (pinfunction "4_4") (pintype "passive"))
      (node (ref "SW27") (pin "3") (pinfunction "3_3") (pintype "passive"))
      (node (ref "SW27") (pin "4") (pinfunction "4_4") (pintype "passive"))
      (node (ref "SW28") (pin "3") (pinfunction "3_3") (pintype "passive"))
      (node (ref "SW28") (pin "4") (pinfunction "4_4") (pintype "passive"))
      (node (ref "SW29") (pin "3") (pinfunction "3_3") (pintype "passive"))
      (node (ref "SW29") (pin "4") (pinfunction "4_4") (pintype "passive"))
      (node (ref "U10") (pin "8") (pinfunction "PC4_8") (pintype "bidirectional"))
      (node (ref "U9") (pin "3") (pinfunction "A_3") (pintype "input"))
    )
    (net (code "35") (name "/PC5") (class "Default")
      (node (ref "SW30") (pin "3") (pinfunction "3_3") (pintype "passive"))
      (node (ref "SW30") (pin "4") (pinfunction "4_4") (pintype "passive"))
      (node (ref "SW31") (pin "3") (pinfunction "3_3") (pintype "passive"))
      (node (ref "SW31") (pin "4") (pinfunction "4_4") (pintype "passive"))
      (node (ref "SW32") (pin "3") (pinfunction "3_3") (pintype "passive"))
      (node (ref "SW32") (pin "4") (pinfunction "4_4") (pintype "passive"))
      (node (ref "SW33") (pin "3") (pinfunction "3_3") (pintype "passive"))
      (node (ref "SW33") (pin "4") (pinfunction "4_4") (pintype "passive"))
      (node (ref "SW34") (pin "3") (pinfunction "3_3") (pintype "passive"))
      (node (ref "SW34") (pin "4") (pinfunction "4_4") (pintype "passive"))
      (node (ref "SW35") (pin "3") (pinfunction "3_3") (pintype "passive"))
      (node (ref "SW35") (pin "4") (pinfunction "4_4") (pintype "passive"))
      (node (ref "U10") (pin "7") (pinfunction "PC5_7") (pintype "bidirectional"))
      (node (ref "U9") (pin "1") (pinfunction "A_1") (pintype "input"))
    )
    (net (code "36") (name "/USER") (class "Default")
      (node (ref "U10") (pin "36") (pinfunction "PA6_36") (pintype "bidirectional"))
    )
    (net (code "37") (name "/~{RD}") (class "Default")
      (node (ref "U10") (pin "44") (pinfunction "~{RD}_44") (pintype "input"))
    )
    (net (code "38") (name "/~{WR}") (class "Default")
      (node (ref "U10") (pin "34") (pinfunction "~{WR}_34") (pintype "input"))
    )
    (net (code "39") (name "GND") (class "Default")
      (node (ref "C14") (pin "2") (pinfunction "2_2") (pintype "passive"))
      (node (ref "C15") (pin "2") (pinfunction "2_2") (pintype "passive"))
      (node (ref "C16") (pin "2") (pinfunction "2_2") (pintype "passive"))
      (node (ref "C17") (pin "1") (pinfunction "1_1") (pintype "passive"))
      (node (ref "J1") (pin "4") (pinfunction "GND_4") (pintype "power_in"))
      (node (ref "J1") (pin "5") (pinfunction "SHLD_5") (pintype "passive"))
      (node (ref "J1") (pin "6") (pinfunction "SHLD_6") (pintype "passive"))
      (node (ref "J1") (pin "7") (pinfunction "SHLD_7") (pintype "passive"))
      (node (ref "J1") (pin "8") (pinfunction "SHLD_8") (pintype "passive"))
      (node (ref "J1") (pin "9") (pinfunction "SHLD_9") (pintype "passive"))
      (node (ref "R25") (pin "2") (pinfunction "2_2") (pintype "passive"))
      (node (ref "R26") (pin "2") (pinfunction "2_2") (pintype "passive"))
      (node (ref "TP14") (pin "TP") (pinfunction "TP_TP") (pintype "passive"))
      (node (ref "U10") (pin "2") (pinfunction "GND_2") (pintype "power_in"))
      (node (ref "U12") (pin "13") (pinfunction "GND_13") (pintype "power_in"))
      (node (ref "U12") (pin "5") (pinfunction "GND_5") (pintype "power_in"))
      (node (ref "U8") (pin "10") (pinfunction "GND_10") (pintype "power_in"))
      (node (ref "U9") (pin "7") (pinfunction "GND_7") (pintype "power_in"))
    )
    (net (code "40") (name "Net-(D2-K)") (class "Default")
      (node (ref "D2") (pin "2") (pinfunction "K_2") (pintype "passive"))
      (node (ref "R36") (pin "2") (pinfunction "2_2") (pintype "passive"))
    )
    (net (code "41") (name "Net-(D3-K)") (class "Default")
      (node (ref "D3") (pin "2") (pinfunction "K_2") (pintype "passive"))
      (node (ref "R37") (pin "1") (pinfunction "1_1") (pintype "passive"))
    )
    (net (code "42") (name "Net-(J1-D+)") (class "Default")
      (node (ref "J1") (pin "3") (pinfunction "D+_3") (pintype "input"))
      (node (ref "R34") (pin "1") (pinfunction "1_1") (pintype "passive"))
    )
    (net (code "43") (name "Net-(J1-D-)") (class "Default")
      (node (ref "J1") (pin "2") (pinfunction "D-_2") (pintype "input"))
      (node (ref "R32") (pin "1") (pinfunction "1_1") (pintype "passive"))
    )
    (net (code "44") (name "Net-(J1-VBUS)") (class "Default")
      (node (ref "C14") (pin "1") (pinfunction "1_1") (pintype "passive"))
      (node (ref "J1") (pin "1") (pinfunction "VBUS_1") (pintype "power_in"))
      (node (ref "L1") (pin "1") (pinfunction "1_1") (pintype "passive"))
    )
    (net (code "45") (name "Net-(U8-Y1)") (class "Default")
      (node (ref "R11") (pin "1") (pinfunction "1_1") (pintype "passive"))
      (node (ref "U8") (pin "18") (pinfunction "Y1_18") (pintype "tri_state"))
    )
    (net (code "46") (name "Net-(U8-Y2)") (class "Default")
      (node (ref "R12") (pin "1") (pinfunction "1_1") (pintype "passive"))
      (node (ref "U8") (pin "17") (pinfunction "Y2_17") (pintype "tri_state"))
    )
    (net (code "47") (name "Net-(U8-Y3)") (class "Default")
      (node (ref "R13") (pin "1") (pinfunction "1_1") (pintype "passive"))
      (node (ref "U8") (pin "16") (pinfunction "Y3_16") (pintype "tri_state"))
    )
    (net (code "48") (name "Net-(U8-Y4)") (class "Default")
      (node (ref "R14") (pin "1") (pinfunction "1_1") (pintype "passive"))
      (node (ref "U8") (pin "15") (pinfunction "Y4_15") (pintype "tri_state"))
    )
    (net (code "49") (name "Net-(U8-Y5)") (class "Default")
      (node (ref "R15") (pin "1") (pinfunction "1_1") (pintype "passive"))
      (node (ref "U8") (pin "14") (pinfunction "Y5_14") (pintype "tri_state"))
    )
    (net (code "50") (name "Net-(U8-Y6)") (class "Default")
      (node (ref "R16") (pin "1") (pinfunction "1_1") (pintype "passive"))
      (node (ref "U8") (pin "13") (pinfunction "Y6_13") (pintype "tri_state"))
    )
    (net (code "51") (name "Net-(U8-Y7)") (class "Default")
      (node (ref "R17") (pin "1") (pinfunction "1_1") (pintype "passive"))
      (node (ref "U8") (pin "12") (pinfunction "Y7_12") (pintype "tri_state"))
    )
    (net (code "52") (name "Net-(U8-Y8)") (class "Default")
      (node (ref "R18") (pin "1") (pinfunction "1_1") (pintype "passive"))
      (node (ref "U8") (pin "11") (pinfunction "Y8_11") (pintype "tri_state"))
    )
    (net (code "53") (name "Net-(U8-~{OE}1)") (class "Default")
      (node (ref "R25") (pin "1") (pinfunction "1_1") (pintype "passive"))
      (node (ref "U8") (pin "1") (pinfunction "~{OE}1_1") (pintype "input"))
    )
    (net (code "54") (name "Net-(U8-~{OE}2)") (class "Default")
      (node (ref "R26") (pin "1") (pinfunction "1_1") (pintype "passive"))
      (node (ref "U8") (pin "19") (pinfunction "~{OE}2_19") (pintype "input"))
    )
    (net (code "55") (name "Net-(U9A-Y)") (class "Default")
      (node (ref "DS1") (pin "3") (pinfunction "K_3") (pintype "passive"))
      (node (ref "DS1") (pin "8") (pinfunction "K_8") (pintype "passive"))
      (node (ref "U9") (pin "2") (pinfunction "Y_2") (pintype "output"))
    )
    (net (code "56") (name "Net-(U9B-Y)") (class "Default")
      (node (ref "DS2") (pin "3") (pinfunction "K_3") (pintype "passive"))
      (node (ref "DS2") (pin "8") (pinfunction "K_8") (pintype "passive"))
      (node (ref "U9") (pin "4") (pinfunction "Y_4") (pintype "output"))
    )
    (net (code "57") (name "Net-(U9C-Y)") (class "Default")
      (node (ref "DS3") (pin "3") (pinfunction "K_3") (pintype "passive"))
      (node (ref "DS3") (pin "8") (pinfunction "K_8") (pintype "passive"))
      (node (ref "U9") (pin "6") (pinfunction "Y_6") (pintype "output"))
    )
    (net (code "58") (name "Net-(U9D-Y)") (class "Default")
      (node (ref "DS4") (pin "3") (pinfunction "K_3") (pintype "passive"))
      (node (ref "DS4") (pin "8") (pinfunction "K_8") (pintype "passive"))
      (node (ref "U9") (pin "8") (pinfunction "Y_8") (pintype "output"))
    )
    (net (code "59") (name "Net-(U9E-Y)") (class "Default")
      (node (ref "DS5") (pin "3") (pinfunction "K_3") (pintype "passive"))
      (node (ref "DS5") (pin "8") (pinfunction "K_8") (pintype "passive"))
      (node (ref "U9") (pin "10") (pinfunction "Y_10") (pintype "output"))
    )
    (net (code "60") (name "Net-(U9F-Y)") (class "Default")
      (node (ref "DS6") (pin "3") (pinfunction "K_3") (pintype "passive"))
      (node (ref "DS6") (pin "8") (pinfunction "K_8") (pintype "passive"))
      (node (ref "U9") (pin "12") (pinfunction "Y_12") (pintype "output"))
    )
    (net (code "61") (name "Net-(U10-PB0)") (class "Default")
      (node (ref "U10") (pin "14") (pinfunction "PB0_14") (pintype "bidirectional"))
      (node (ref "U8") (pin "2") (pinfunction "A1_2") (pintype "input"))
    )
    (net (code "62") (name "Net-(U10-PB1)") (class "Default")
      (node (ref "U10") (pin "15") (pinfunction "PB1_15") (pintype "bidirectional"))
      (node (ref "U8") (pin "3") (pinfunction "A2_3") (pintype "input"))
    )
    (net (code "63") (name "Net-(U10-PB2)") (class "Default")
      (node (ref "U10") (pin "16") (pinfunction "PB2_16") (pintype "bidirectional"))
      (node (ref "U8") (pin "4") (pinfunction "A3_4") (pintype "input"))
    )
    (net (code "64") (name "Net-(U10-PB3)") (class "Default")
      (node (ref "U10") (pin "18") (pinfunction "PB3_18") (pintype "bidirectional"))
      (node (ref "U8") (pin "5") (pinfunction "A4_5") (pintype "input"))
    )
    (net (code "65") (name "Net-(U10-PB4)") (class "Default")
      (node (ref "U10") (pin "19") (pinfunction "PB4_19") (pintype "bidirectional"))
      (node (ref "U8") (pin "6") (pinfunction "A5_6") (pintype "input"))
    )
    (net (code "66") (name "Net-(U10-PB5)") (class "Default")
      (node (ref "U10") (pin "20") (pinfunction "PB5_20") (pintype "bidirectional"))
      (node (ref "U8") (pin "7") (pinfunction "A6_7") (pintype "input"))
    )
    (net (code "67") (name "Net-(U10-PB6)") (class "Default")
      (node (ref "U10") (pin "21") (pinfunction "PB6_21") (pintype "bidirectional"))
      (node (ref "U8") (pin "8") (pinfunction "A7_8") (pintype "input"))
    )
    (net (code "68") (name "Net-(U10-PB7)") (class "Default")
      (node (ref "U10") (pin "23") (pinfunction "PB7_23") (pintype "bidirectional"))
      (node (ref "U8") (pin "9") (pinfunction "A8_9") (pintype "input"))
    )
    (net (code "69") (name "Net-(U12-3V3OUT)") (class "Default")
      (node (ref "C17") (pin "2") (pinfunction "2_2") (pintype "passive"))
      (node (ref "U12") (pin "10") (pinfunction "3V3OUT_10") (pintype "power_in"))
      (node (ref "U12") (pin "11") (pinfunction "RESET#_11") (pintype "input"))
      (node (ref "U12") (pin "3") (pinfunction "VCCIO_3") (pintype "power_in"))
    )
    (net (code "70") (name "Net-(U12-CBUS0)") (class "Default")
      (node (ref "R36") (pin "1") (pinfunction "1_1") (pintype "passive"))
      (node (ref "TP3") (pin "TP") (pinfunction "TP_TP") (pintype "passive"))
      (node (ref "U12") (pin "15") (pinfunction "CBUS0_15") (pintype "bidirectional"))
    )
    (net (code "71") (name "Net-(U12-CBUS1)") (class "Default")
      (node (ref "R37") (pin "2") (pinfunction "2_2") (pintype "passive"))
      (node (ref "TP4") (pin "TP") (pinfunction "TP_TP") (pintype "passive"))
      (node (ref "U12") (pin "14") (pinfunction "CBUS1_14") (pintype "bidirectional"))
    )
    (net (code "72") (name "Net-(U12-CBUS2)") (class "Default")
      (node (ref "TP5") (pin "TP") (pinfunction "TP_TP") (pintype "passive"))
      (node (ref "U12") (pin "7") (pinfunction "CBUS2_7") (pintype "bidirectional"))
    )
    (net (code "73") (name "Net-(U12-CBUS3)") (class "Default")
      (node (ref "TP6") (pin "TP") (pinfunction "TP_TP") (pintype "passive"))
      (node (ref "U12") (pin "16") (pinfunction "CBUS3_16") (pintype "bidirectional"))
    )
    (net (code "74") (name "Net-(U12-CBUS4)") (class "Default")
      (node (ref "TP7") (pin "TP") (pinfunction "TP_TP") (pintype "passive"))
      (node (ref "U12") (pin "6") (pinfunction "CBUS4_6") (pintype "bidirectional"))
    )
    (net (code "75") (name "Net-(U12-CBUS5)") (class "Default")
      (node (ref "TP8") (pin "TP") (pinfunction "TP_TP") (pintype "passive"))
      (node (ref "U12") (pin "1") (pinfunction "CBUS5_1") (pintype "bidirectional"))
    )
    (net (code "76") (name "Net-(U12-SCL)") (class "Default")
      (node (ref "R33") (pin "1") (pinfunction "1_1") (pintype "passive"))
      (node (ref "U12") (pin "2") (pinfunction "SCL_2") (pintype "input"))
    )
    (net (code "77") (name "Net-(U12-SDA)") (class "Default")
      (node (ref "R35") (pin "1") (pinfunction "1_1") (pintype "passive"))
      (node (ref "U12") (pin "4") (pinfunction "SDA_4") (pintype "bidirectional"))
    )
    (net (code "78") (name "Net-(U12-USBDM)") (class "Default")
      (node (ref "C16") (pin "1") (pinfunction "1_1") (pintype "passive"))
      (node (ref "R32") (pin "2") (pinfunction "2_2") (pintype "passive"))
      (node (ref "U12") (pin "9") (pinfunction "USBDM_9") (pintype "input"))
    )
    (net (code "79") (name "Net-(U12-USBDP)") (class "Default")
      (node (ref "C15") (pin "1") (pinfunction "1_1") (pintype "passive"))
      (node (ref "R34") (pin "2") (pinfunction "2_2") (pintype "passive"))
      (node (ref "U12") (pin "8") (pinfunction "USBDP_8") (pintype "input"))
    )
    (net (code "80") (name "VCC") (class "Default")
      (node (ref "D2") (pin "1") (pinfunction "A_1") (pintype "passive"))
      (node (ref "D3") (pin "1") (pinfunction "A_1") (pintype "passive"))
      (node (ref "L1") (pin "2") (pinfunction "2_2") (pintype "passive"))
      (node (ref "R19") (pin "2") (pinfunction "2_2") (pintype "passive"))
      (node (ref "R20") (pin "2") (pinfunction "2_2") (pintype "passive"))
      (node (ref "R21") (pin "2") (pinfunction "2_2") (pintype "passive"))
      (node (ref "R22") (pin "2") (pinfunction "2_2") (pintype "passive"))
      (node (ref "R23") (pin "2") (pinfunction "2_2") (pintype "passive"))
      (node (ref "R24") (pin "2") (pinfunction "2_2") (pintype "passive"))
      (node (ref "R30") (pin "2") (pinfunction "2_2") (pintype "passive"))
      (node (ref "R31") (pin "2") (pinfunction "2_2") (pintype "passive"))
      (node (ref "TP13") (pin "TP") (pinfunction "TP_TP") (pintype "passive"))
      (node (ref "U10") (pin "24") (pinfunction "VCC_24") (pintype "power_in"))
      (node (ref "U12") (pin "12") (pinfunction "VCC_12") (pintype "power_in"))
      (node (ref "U8") (pin "20") (pinfunction "VCC_20") (pintype "power_in"))
      (node (ref "U9") (pin "14") (pinfunction "VCC_14") (pintype "power_in"))
    )
    (net (code "81") (name "unconnected-(U10-NC-Pad12)") (class "Default")
      (node (ref "U10") (pin "12") (pinfunction "NC_12") (pintype "passive"))
    )
    (net (code "82") (name "unconnected-(U10-NC-Pad17)") (class "Default")
      (node (ref "U10") (pin "17") (pinfunction "NC_17") (pintype "passive"))
    )
    (net (code "83") (name "unconnected-(U10-NC-Pad22)") (class "Default")
      (node (ref "U10") (pin "22") (pinfunction "NC_22") (pintype "passive"))
    )
    (net (code "84") (name "unconnected-(U10-NC-Pad39)") (class "Default")
      (node (ref "U10") (pin "39") (pinfunction "NC_39") (pintype "passive"))
    )
  )
)
